# STALO_3.net
KiCad netlist of a schematic drawn in Altium Designer
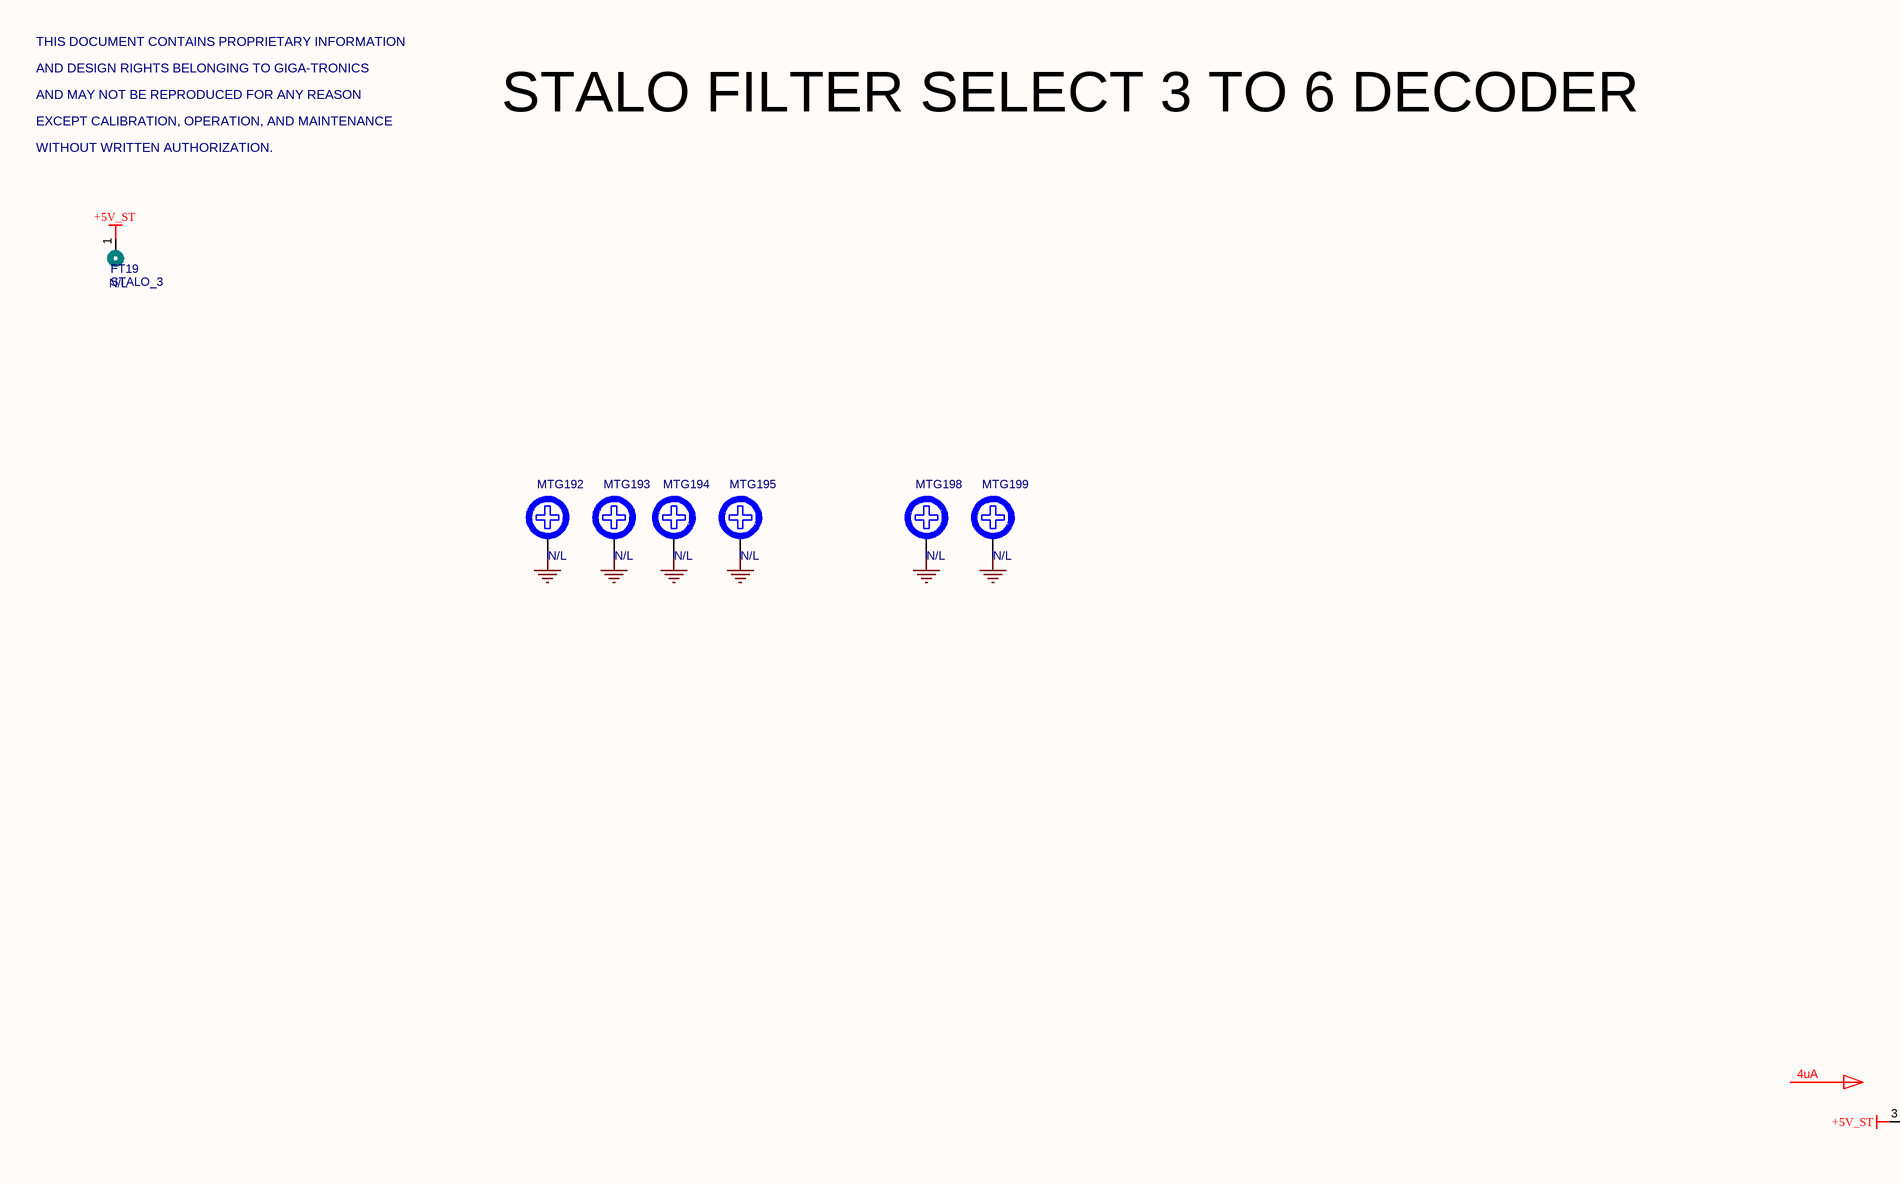
[diagram p0: STALO_3.SchDoc, top left]
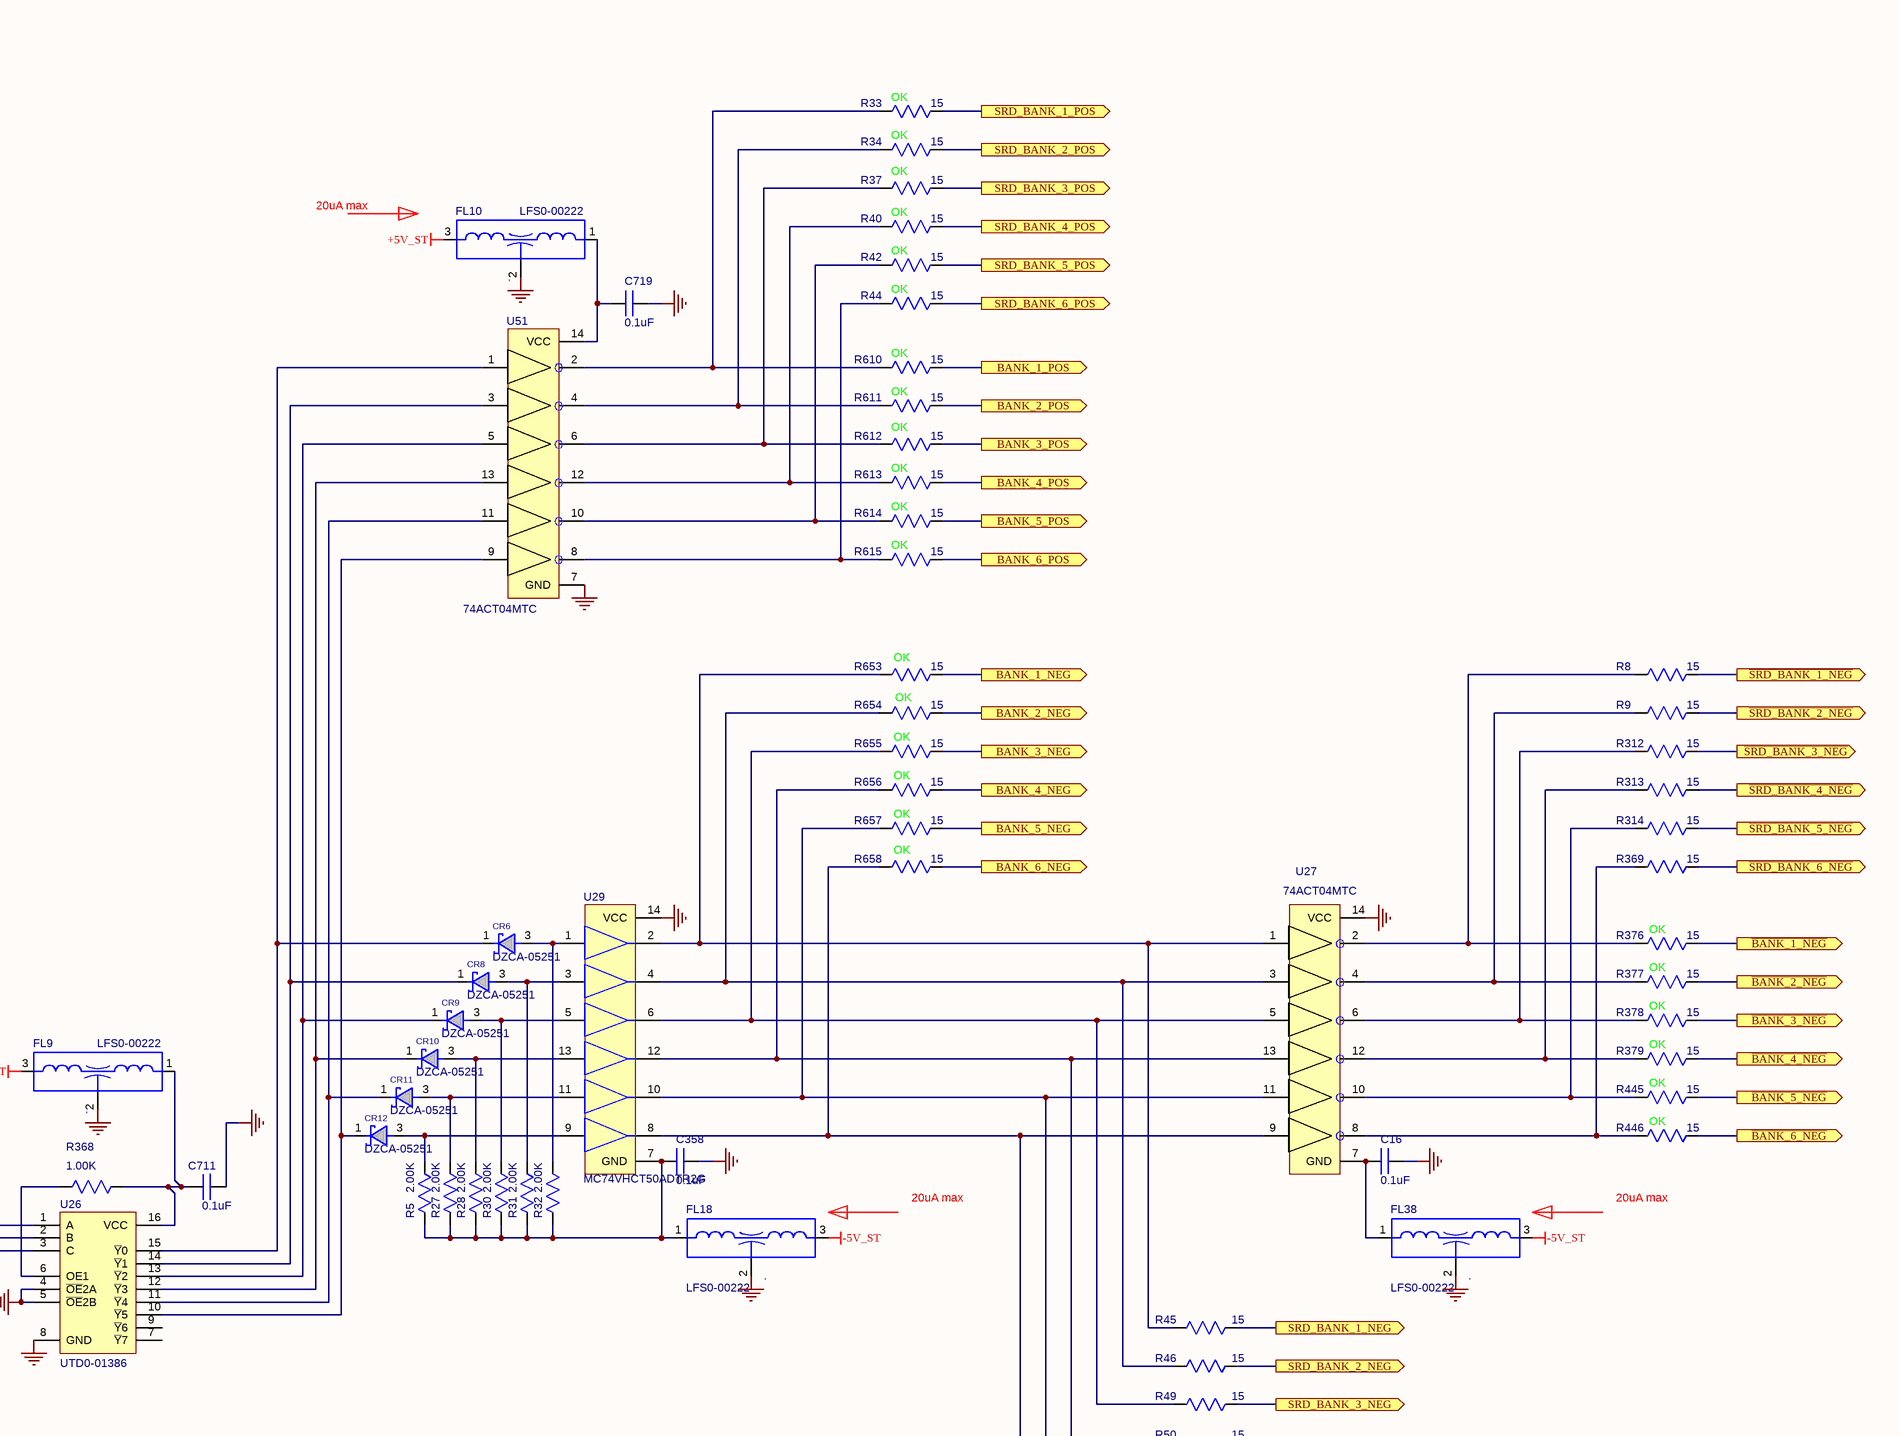
[diagram p1: STALO_3.SchDoc, top right]
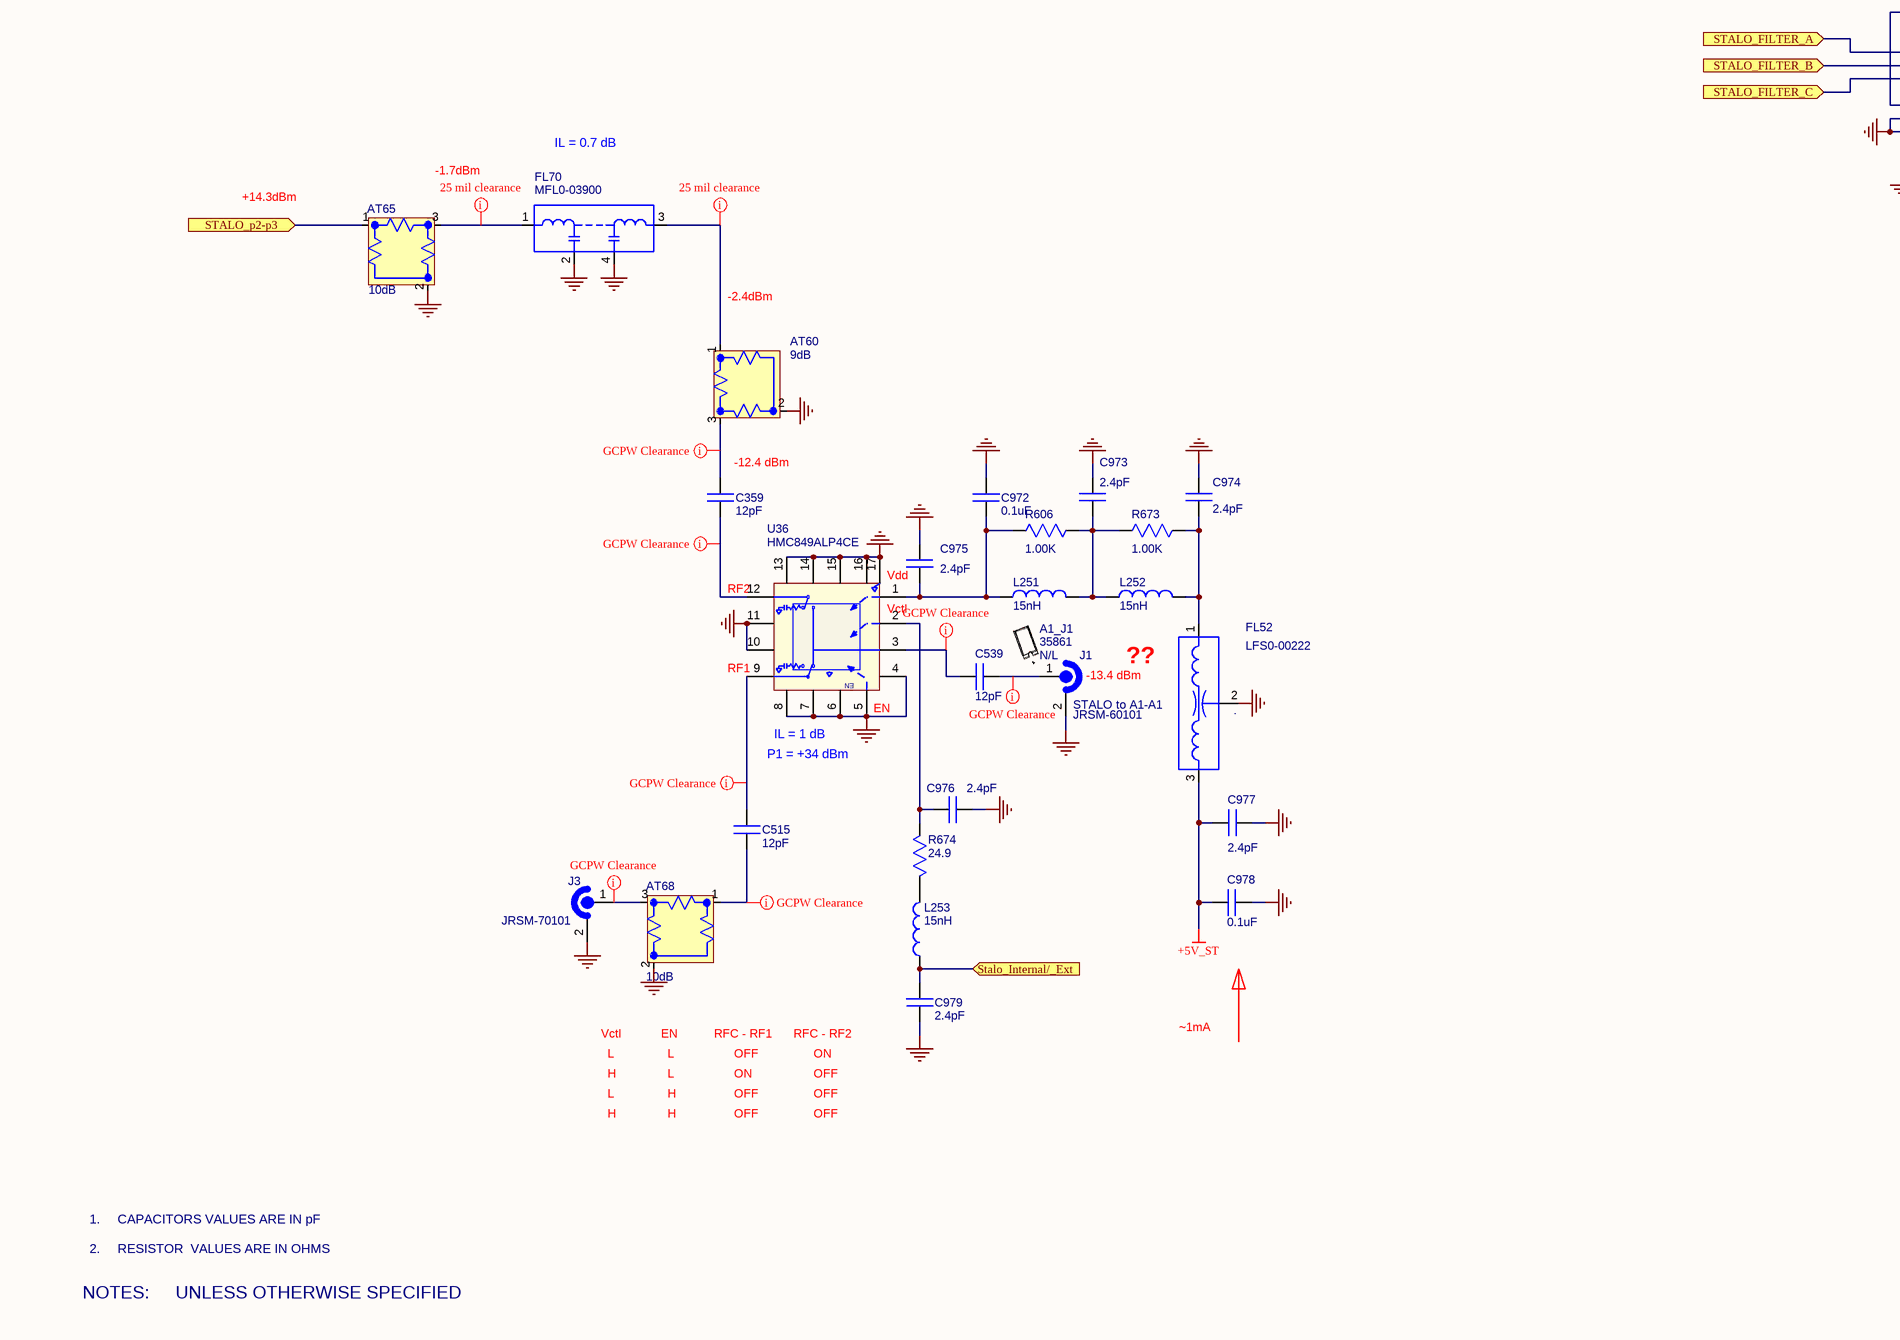
[diagram p2: STALO_3.SchDoc, bottom left]
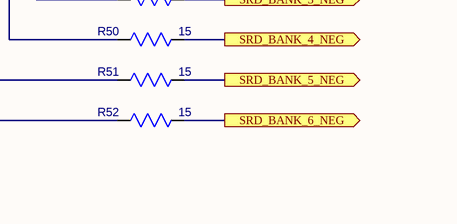
[diagram p3: STALO_3.SchDoc, bottom right]

(export (version "E")
  (design (tool "Eeschema 10.0.6"))
  (components
    (comp (ref "A1_J1")
      (value "35861")
      (footprint "35861")
      (description "SHIELD,HYDRA,A1-J1")
      (fields (field (name "NOLOAD") "N/L") (field (name "G_PN") "35861"))
      (libsource (lib "Hydra_Ref_sch") (part "35861"))
    )
    (comp (ref "AT60")
      (value "9dB")
      (footprint "ATTN-IMS-0805")
      (description "PAD;CHIP;9dB;+/-.3dB;.08 x .05;50 OHM;FACE DOWN")
      (libsource (lib "Giga-tronics") (part "MPFC-A1009"))
    )
    (comp (ref "AT65")
      (value "10dB")
      (footprint "ATTN-IMS-0805")
      (description "PAD;CHIP;10dB;+/-.3dB;.08 x .05;50 OHM;FACE DOWN")
      (libsource (lib "") (part "MPFC-A1010_1"))
    )
    (comp (ref "AT68")
      (value "10dB")
      (footprint "ATTN-IMS-0805")
      (description "PAD;CHIP;10dB;+/-.3dB;.08 x .05;50 OHM;FACE DOWN")
      (libsource (lib "Giga-tronics") (part "MPFC-A1010"))
    )
    (comp (ref "C16")
      (value "0.1uF")
      (footprint "CAP-0402-N")
      (description ".1 UF,10%;X7R;16V,CHIP;0402")
      (libsource (lib "Giga-tronics") (part "CK40-04100"))
    )
    (comp (ref "C358")
      (value "0.1uF")
      (footprint "CAP-0402-N")
      (description ".1 UF,10%;X7R;16V,CHIP;0402")
      (libsource (lib "Giga-tronics") (part "CK40-04100"))
    )
    (comp (ref "C359")
      (value "12pF")
      (footprint "CAP-0402-N")
      (description "12 PF;5%;COG;>50V;CHIP;0402")
      (libsource (lib "Giga-tronics") (part "CK40-00120"))
    )
    (comp (ref "C515")
      (value "12pF")
      (footprint "CAP-0402-N")
      (description "12 PF;5%;COG;>50V;CHIP;0402")
      (libsource (lib "Giga-tronics") (part "CK40-00120"))
    )
    (comp (ref "C539")
      (value "12pF")
      (footprint "CAP-0402-N")
      (description "12 PF;5%;COG;>50V;CHIP;0402")
      (libsource (lib "Giga-tronics") (part "CK40-00120"))
    )
    (comp (ref "C711")
      (value "0.1uF")
      (footprint "CAP-0402-N")
      (description ".1 UF,10%;X7R;16V,CHIP;0402")
      (libsource (lib "Giga-tronics") (part "CK40-04100"))
    )
    (comp (ref "C719")
      (value "0.1uF")
      (footprint "CAP-0402-N")
      (description ".1 UF,10%;X7R;16V,CHIP;0402")
      (libsource (lib "Giga-tronics") (part "CK40-04100"))
    )
    (comp (ref "C972")
      (value "0.1uF")
      (footprint "CAP-0402-N")
      (description ".1 UF,10%;X7R;16V,CHIP;0402")
      (libsource (lib "Giga-tronics") (part "CK40-04100"))
    )
    (comp (ref "C973")
      (value "2.4pF")
      (footprint "CAP-0402-RF")
      (description "2.4 PF;200V;.05PF;HIGH Q;SMT;CERAMIC;0402")
      (libsource (lib "Giga-tronics") (part "CK41-00024"))
    )
    (comp (ref "C974")
      (value "2.4pF")
      (footprint "CAP-0402-RF")
      (description "2.4 PF;200V;.05PF;HIGH Q;SMT;CERAMIC;0402")
      (libsource (lib "Giga-tronics") (part "CK41-00024"))
    )
    (comp (ref "C975")
      (value "2.4pF")
      (footprint "CAP-0402-RF")
      (description "2.4 PF;200V;.05PF;HIGH Q;SMT;CERAMIC;0402")
      (libsource (lib "Giga-tronics") (part "CK41-00024"))
    )
    (comp (ref "C976")
      (value "2.4pF")
      (footprint "CAP-0402-RF")
      (description "2.4 PF;200V;.05PF;HIGH Q;SMT;CERAMIC;0402")
      (libsource (lib "Giga-tronics") (part "CK41-00024"))
    )
    (comp (ref "C977")
      (value "2.4pF")
      (footprint "CAP-0402-RF")
      (description "2.4 PF;200V;.05PF;HIGH Q;SMT;CERAMIC;0402")
      (libsource (lib "Giga-tronics") (part "CK41-00024"))
    )
    (comp (ref "C978")
      (value "0.1uF")
      (footprint "CAP-0402-N")
      (description ".1 UF,10%;X7R;16V,CHIP;0402")
      (libsource (lib "Giga-tronics") (part "CK40-04100"))
    )
    (comp (ref "C979")
      (value "2.4pF")
      (footprint "CAP-0402-RF")
      (description "2.4 PF;200V;.05PF;HIGH Q;SMT;CERAMIC;0402")
      (libsource (lib "Giga-tronics") (part "CK41-00024"))
    )
    (comp (ref "CR6")
      (value "5.1V;5%;.15W;Z=20;0603")
      (footprint "DO-0603-SOD-523F")
      (fields (field (name "G_PN") "DZCA-05251"))
      (libsource (lib "Giga-tronics") (part "DZCA-05251"))
    )
    (comp (ref "CR8")
      (value "5.1V;5%;.15W;Z=20;0603")
      (footprint "DO-0603-SOD-523F")
      (fields (field (name "G_PN") "DZCA-05251"))
      (libsource (lib "Giga-tronics") (part "DZCA-05251"))
    )
    (comp (ref "CR9")
      (value "5.1V;5%;.15W;Z=20;0603")
      (footprint "DO-0603-SOD-523F")
      (fields (field (name "G_PN") "DZCA-05251"))
      (libsource (lib "Giga-tronics") (part "DZCA-05251"))
    )
    (comp (ref "CR10")
      (value "5.1V;5%;.15W;Z=20;0603")
      (footprint "DO-0603-SOD-523F")
      (fields (field (name "G_PN") "DZCA-05251"))
      (libsource (lib "Giga-tronics") (part "DZCA-05251"))
    )
    (comp (ref "CR11")
      (value "5.1V;5%;.15W;Z=20;0603")
      (footprint "DO-0603-SOD-523F")
      (fields (field (name "G_PN") "DZCA-05251"))
      (libsource (lib "Giga-tronics") (part "DZCA-05251"))
    )
    (comp (ref "CR12")
      (value "5.1V;5%;.15W;Z=20;0603")
      (footprint "DO-0603-SOD-523F")
      (fields (field (name "G_PN") "DZCA-05251"))
      (libsource (lib "Giga-tronics") (part "DZCA-05251"))
    )
    (comp (ref "FL9")
      (value "Filter EMI 2200PF,1206")
      (footprint "FIL-NFE31P-1206-4P")
      (fields (field (name "G_PN") "LFS0-00222"))
      (libsource (lib "Giga-tronics") (part "LFS0-00222"))
    )
    (comp (ref "FL10")
      (value "Filter EMI 2200PF,1206")
      (footprint "FIL-NFE31P-1206-4P")
      (fields (field (name "G_PN") "LFS0-00222"))
      (libsource (lib "Giga-tronics") (part "LFS0-00222"))
    )
    (comp (ref "FL18")
      (value "Filter EMI 2200PF,1206")
      (footprint "FIL-NFE31P-1206-4P")
      (fields (field (name "G_PN") "LFS0-00222"))
      (libsource (lib "") (part "LFS0-00222_1"))
    )
    (comp (ref "FL38")
      (value "Filter EMI 2200PF,1206")
      (footprint "FIL-NFE31P-1206-4P")
      (fields (field (name "G_PN") "LFS0-00222"))
      (libsource (lib "") (part "LFS0-00222_1"))
    )
    (comp (ref "FL52")
      (value "Filter EMI 2200PF,1206")
      (footprint "FIL-NFE31P-1206-4P")
      (fields (field (name "G_PN") "LFS0-00222"))
      (libsource (lib "Giga-tronics") (part "LFS0-00222"))
    )
    (comp (ref "FL70")
      (value "FILTER;LOW PASS;3900MHz;7SEC;FV1206")
      (footprint "FV1206")
      (fields (field (name "G_PN") "MFL0-03900"))
      (libsource (lib "Giga-tronics") (part "MFL0-03900"))
    )
    (comp (ref "FT19")
      (value "STALO_3")
      (footprint "FromToNode_ML2")
      (fields (field (name "NOLOAD") "N/L"))
      (libsource (lib "Giga-tronics") (part "FromToNode"))
    )
    (comp (ref "J1")
      (value "STALO to A1-A1")
      (footprint "JRSM-60101")
      (description "SMPM SM MALE,STRAIGHT SMT, R/A COPLANAR, 4 PIN THRU-HOLE")
      (fields (field (name "G_PN") "JRSM-60101"))
      (libsource (lib "Giga-tronics") (part "JRSM-60101"))
    )
    (comp (ref "J3")
      (value ".")
      (footprint "JRSM-70101")
      (description "SMPM FD MALE,STRAIGHT SMT, R/A COPLANAR, 4 PIN THRU-HOLE")
      (fields (field (name "G_PN") "JRSM-70101"))
      (libsource (lib "Giga-tronics") (part "JRSM-70101"))
    )
    (comp (ref "L251")
      (value "15nH")
      (footprint "IND-0402HP")
      (description "INDUCTOR;15NH;2%;3.9GHZ SRF;85Q @1.7GHZ;.078 DCR;1.1A;0402")
      (libsource (lib "Giga-tronics") (part "LSA6-03150"))
    )
    (comp (ref "L252")
      (value "15nH")
      (footprint "IND-0402HP")
      (description "INDUCTOR;15NH;2%;3.9GHZ SRF;85Q @1.7GHZ;.078 DCR;1.1A;0402")
      (libsource (lib "Giga-tronics") (part "LSA6-03150"))
    )
    (comp (ref "L253")
      (value "15nH")
      (footprint "IND-0402HP")
      (description "INDUCTOR;15NH;2%;3.9GHZ SRF;85Q @1.7GHZ;.078 DCR;1.1A;0402")
      (libsource (lib "") (part "LSA6-03150_1"))
    )
    (comp (ref "MTG192")
      (value "~")
      (footprint "MHP200X92")
      (description "MHP200X92")
      (fields (field (name "NOLOAD") "N/L"))
      (libsource (lib "Giga-tronics") (part "MHP200X92"))
    )
    (comp (ref "MTG193")
      (value "~")
      (footprint "MHP200X92")
      (description "MHP200X92")
      (fields (field (name "NOLOAD") "N/L"))
      (libsource (lib "Giga-tronics") (part "MHP200X92"))
    )
    (comp (ref "MTG194")
      (value "~")
      (footprint "MHP200X92")
      (description "MHP200X92")
      (fields (field (name "NOLOAD") "N/L"))
      (libsource (lib "Giga-tronics") (part "MHP200X92"))
    )
    (comp (ref "MTG195")
      (value "~")
      (footprint "MHP200X92")
      (description "MHP200X92")
      (fields (field (name "NOLOAD") "N/L"))
      (libsource (lib "Giga-tronics") (part "MHP200X92"))
    )
    (comp (ref "MTG198")
      (value "~")
      (footprint "MHP200X92")
      (description "MHP200X92")
      (fields (field (name "NOLOAD") "N/L"))
      (libsource (lib "Giga-tronics") (part "MHP200X92"))
    )
    (comp (ref "MTG199")
      (value "~")
      (footprint "MHP200X92")
      (description "MHP200X92")
      (fields (field (name "NOLOAD") "N/L"))
      (libsource (lib "Giga-tronics") (part "MHP200X92"))
    )
    (comp (ref "R5")
      (value "2.00K")
      (footprint "RES-0402-N")
      (description "2.00K OHMS;.06W;1%;200PPM;FILM;CHIP;0402")
      (libsource (lib "Giga-tronics") (part "RK35-12000"))
    )
    (comp (ref "R8")
      (value "15")
      (footprint "RES-0402-N")
      (description "15 OHMS;.06W;1%;200PPM;FILM;CHIP;0402")
      (libsource (lib "Giga-tronics") (part "RK35-00150"))
    )
    (comp (ref "R9")
      (value "15")
      (footprint "RES-0402-N")
      (description "15 OHMS;.06W;1%;200PPM;FILM;CHIP;0402")
      (libsource (lib "Giga-tronics") (part "RK35-00150"))
    )
    (comp (ref "R27")
      (value "2.00K")
      (footprint "RES-0402-N")
      (description "2.00K OHMS;.06W;1%;200PPM;FILM;CHIP;0402")
      (libsource (lib "Giga-tronics") (part "RK35-12000"))
    )
    (comp (ref "R28")
      (value "2.00K")
      (footprint "RES-0402-N")
      (description "2.00K OHMS;.06W;1%;200PPM;FILM;CHIP;0402")
      (libsource (lib "Giga-tronics") (part "RK35-12000"))
    )
    (comp (ref "R30")
      (value "2.00K")
      (footprint "RES-0402-N")
      (description "2.00K OHMS;.06W;1%;200PPM;FILM;CHIP;0402")
      (libsource (lib "Giga-tronics") (part "RK35-12000"))
    )
    (comp (ref "R31")
      (value "2.00K")
      (footprint "RES-0402-N")
      (description "2.00K OHMS;.06W;1%;200PPM;FILM;CHIP;0402")
      (libsource (lib "Giga-tronics") (part "RK35-12000"))
    )
    (comp (ref "R32")
      (value "2.00K")
      (footprint "RES-0402-N")
      (description "2.00K OHMS;.06W;1%;200PPM;FILM;CHIP;0402")
      (libsource (lib "Giga-tronics") (part "RK35-12000"))
    )
    (comp (ref "R33")
      (value "15")
      (footprint "RES-0402-N")
      (description "15 OHMS;.06W;1%;200PPM;FILM;CHIP;0402")
      (libsource (lib "Giga-tronics") (part "RK35-00150"))
    )
    (comp (ref "R34")
      (value "15")
      (footprint "RES-0402-N")
      (description "15 OHMS;.06W;1%;200PPM;FILM;CHIP;0402")
      (libsource (lib "Giga-tronics") (part "RK35-00150"))
    )
    (comp (ref "R37")
      (value "15")
      (footprint "RES-0402-N")
      (description "15 OHMS;.06W;1%;200PPM;FILM;CHIP;0402")
      (libsource (lib "Giga-tronics") (part "RK35-00150"))
    )
    (comp (ref "R40")
      (value "15")
      (footprint "RES-0402-N")
      (description "15 OHMS;.06W;1%;200PPM;FILM;CHIP;0402")
      (libsource (lib "Giga-tronics") (part "RK35-00150"))
    )
    (comp (ref "R42")
      (value "15")
      (footprint "RES-0402-N")
      (description "15 OHMS;.06W;1%;200PPM;FILM;CHIP;0402")
      (libsource (lib "Giga-tronics") (part "RK35-00150"))
    )
    (comp (ref "R44")
      (value "15")
      (footprint "RES-0402-N")
      (description "15 OHMS;.06W;1%;200PPM;FILM;CHIP;0402")
      (libsource (lib "Giga-tronics") (part "RK35-00150"))
    )
    (comp (ref "R45")
      (value "15")
      (footprint "RES-0402-N")
      (description "15 OHMS;.06W;1%;200PPM;FILM;CHIP;0402")
      (libsource (lib "Giga-tronics") (part "RK35-00150"))
    )
    (comp (ref "R46")
      (value "15")
      (footprint "RES-0402-N")
      (description "15 OHMS;.06W;1%;200PPM;FILM;CHIP;0402")
      (libsource (lib "Giga-tronics") (part "RK35-00150"))
    )
    (comp (ref "R49")
      (value "15")
      (footprint "RES-0402-N")
      (description "15 OHMS;.06W;1%;200PPM;FILM;CHIP;0402")
      (libsource (lib "Giga-tronics") (part "RK35-00150"))
    )
    (comp (ref "R50")
      (value "15")
      (footprint "RES-0402-N")
      (description "15 OHMS;.06W;1%;200PPM;FILM;CHIP;0402")
      (libsource (lib "Giga-tronics") (part "RK35-00150"))
    )
    (comp (ref "R51")
      (value "15")
      (footprint "RES-0402-N")
      (description "15 OHMS;.06W;1%;200PPM;FILM;CHIP;0402")
      (libsource (lib "Giga-tronics") (part "RK35-00150"))
    )
    (comp (ref "R52")
      (value "15")
      (footprint "RES-0402-N")
      (description "15 OHMS;.06W;1%;200PPM;FILM;CHIP;0402")
      (libsource (lib "Giga-tronics") (part "RK35-00150"))
    )
    (comp (ref "R312")
      (value "15")
      (footprint "RES-0402-N")
      (description "15 OHMS;.06W;1%;200PPM;FILM;CHIP;0402")
      (libsource (lib "Giga-tronics") (part "RK35-00150"))
    )
    (comp (ref "R313")
      (value "15")
      (footprint "RES-0402-N")
      (description "15 OHMS;.06W;1%;200PPM;FILM;CHIP;0402")
      (libsource (lib "Giga-tronics") (part "RK35-00150"))
    )
    (comp (ref "R314")
      (value "15")
      (footprint "RES-0402-N")
      (description "15 OHMS;.06W;1%;200PPM;FILM;CHIP;0402")
      (libsource (lib "Giga-tronics") (part "RK35-00150"))
    )
    (comp (ref "R368")
      (value "1.00K")
      (footprint "RES-0402-N")
      (description "1.0K OHMS;.06W;1%;200PPM;FILM;CHIP;0402")
      (libsource (lib "Giga-tronics") (part "RK35-11000"))
    )
    (comp (ref "R369")
      (value "15")
      (footprint "RES-0402-N")
      (description "15 OHMS;.06W;1%;200PPM;FILM;CHIP;0402")
      (libsource (lib "Giga-tronics") (part "RK35-00150"))
    )
    (comp (ref "R376")
      (value "15")
      (footprint "RES-0402-N")
      (description "15 OHMS;.06W;1%;200PPM;FILM;CHIP;0402")
      (libsource (lib "Giga-tronics") (part "RK35-00150"))
    )
    (comp (ref "R377")
      (value "15")
      (footprint "RES-0402-N")
      (description "15 OHMS;.06W;1%;200PPM;FILM;CHIP;0402")
      (libsource (lib "Giga-tronics") (part "RK35-00150"))
    )
    (comp (ref "R378")
      (value "15")
      (footprint "RES-0402-N")
      (description "15 OHMS;.06W;1%;200PPM;FILM;CHIP;0402")
      (libsource (lib "Giga-tronics") (part "RK35-00150"))
    )
    (comp (ref "R379")
      (value "15")
      (footprint "RES-0402-N")
      (description "15 OHMS;.06W;1%;200PPM;FILM;CHIP;0402")
      (libsource (lib "Giga-tronics") (part "RK35-00150"))
    )
    (comp (ref "R445")
      (value "15")
      (footprint "RES-0402-N")
      (description "15 OHMS;.06W;1%;200PPM;FILM;CHIP;0402")
      (libsource (lib "Giga-tronics") (part "RK35-00150"))
    )
    (comp (ref "R446")
      (value "15")
      (footprint "RES-0402-N")
      (description "15 OHMS;.06W;1%;200PPM;FILM;CHIP;0402")
      (libsource (lib "Giga-tronics") (part "RK35-00150"))
    )
    (comp (ref "R606")
      (value "1.00K")
      (footprint "RES-0402-N")
      (description "1.0K OHMS;.06W;1%;200PPM;FILM;CHIP;0402")
      (libsource (lib "Giga-tronics") (part "RK35-11000"))
    )
    (comp (ref "R610")
      (value "15")
      (footprint "RES-0402-N")
      (description "15 OHMS;.06W;1%;200PPM;FILM;CHIP;0402")
      (libsource (lib "Giga-tronics") (part "RK35-00150"))
    )
    (comp (ref "R611")
      (value "15")
      (footprint "RES-0402-N")
      (description "15 OHMS;.06W;1%;200PPM;FILM;CHIP;0402")
      (libsource (lib "Giga-tronics") (part "RK35-00150"))
    )
    (comp (ref "R612")
      (value "15")
      (footprint "RES-0402-N")
      (description "15 OHMS;.06W;1%;200PPM;FILM;CHIP;0402")
      (libsource (lib "Giga-tronics") (part "RK35-00150"))
    )
    (comp (ref "R613")
      (value "15")
      (footprint "RES-0402-N")
      (description "15 OHMS;.06W;1%;200PPM;FILM;CHIP;0402")
      (libsource (lib "Giga-tronics") (part "RK35-00150"))
    )
    (comp (ref "R614")
      (value "15")
      (footprint "RES-0402-N")
      (description "15 OHMS;.06W;1%;200PPM;FILM;CHIP;0402")
      (libsource (lib "Giga-tronics") (part "RK35-00150"))
    )
    (comp (ref "R615")
      (value "15")
      (footprint "RES-0402-N")
      (description "15 OHMS;.06W;1%;200PPM;FILM;CHIP;0402")
      (libsource (lib "Giga-tronics") (part "RK35-00150"))
    )
    (comp (ref "R653")
      (value "15")
      (footprint "RES-0402-N")
      (description "15 OHMS;.06W;1%;200PPM;FILM;CHIP;0402")
      (libsource (lib "Giga-tronics") (part "RK35-00150"))
    )
    (comp (ref "R654")
      (value "15")
      (footprint "RES-0402-N")
      (description "15 OHMS;.06W;1%;200PPM;FILM;CHIP;0402")
      (libsource (lib "Giga-tronics") (part "RK35-00150"))
    )
    (comp (ref "R655")
      (value "15")
      (footprint "RES-0402-N")
      (description "15 OHMS;.06W;1%;200PPM;FILM;CHIP;0402")
      (libsource (lib "Giga-tronics") (part "RK35-00150"))
    )
    (comp (ref "R656")
      (value "15")
      (footprint "RES-0402-N")
      (description "15 OHMS;.06W;1%;200PPM;FILM;CHIP;0402")
      (libsource (lib "Giga-tronics") (part "RK35-00150"))
    )
    (comp (ref "R657")
      (value "15")
      (footprint "RES-0402-N")
      (description "15 OHMS;.06W;1%;200PPM;FILM;CHIP;0402")
      (libsource (lib "Giga-tronics") (part "RK35-00150"))
    )
    (comp (ref "R658")
      (value "15")
      (footprint "RES-0402-N")
      (description "15 OHMS;.06W;1%;200PPM;FILM;CHIP;0402")
      (libsource (lib "Giga-tronics") (part "RK35-00150"))
    )
    (comp (ref "R673")
      (value "1.00K")
      (footprint "RES-0402-N")
      (description "1.0K OHMS;.06W;1%;200PPM;FILM;CHIP;0402")
      (libsource (lib "Giga-tronics") (part "RK35-11000"))
    )
    (comp (ref "R674")
      (value "24.9")
      (footprint "RES-0402-N")
      (description "24.9 OHMS;.06W;1%;200PPM;FILM;CHIP;0402")
      (libsource (lib "Giga-tronics") (part "RK35-00249"))
    )
    (comp (ref "U26")
      (value "UTD0-01386")
      (footprint "SOIC16_MS-012")
      (description "3 TO 8 DECODER/DEMULTIPLEXER;74ACT138 LOGIC;SO-16")
      (fields (field (name "G_PN") "UTD0-01386"))
      (libsource (lib "Giga-tronics") (part "UTD0-01386"))
    )
    (comp (ref "U27")
      (value "74ACT04MTC HEX INVERTER;SMT;TSSOP-14")
      (footprint "TSOP65P640X120-14L")
      (fields (field (name "M_PN") "74ACT04MTC"))
      (libsource (lib "Giga-tronics") (part "UTD4-00046"))
    )
    (comp (ref "U29")
      (value "MC74VHCT50A;HEX BUFFERS;3.5NS;TTL INPUTS;TSSOP-14")
      (footprint "TSOP65P640X120-14L")
      (fields (field (name "M_PN") "MC74VHCT50ADTR2G"))
      (libsource (lib "Giga-tronics") (part "UTD0-00050"))
    )
    (comp (ref "U36")
      (value "SWITCH;SPDT;DC-6GHz;50DB ISO;33DBM;3-5V CTRL;QFN-16")
      (footprint "QFN-16_HITTITE_LP4CE")
      (fields (field (name "M_PN") "HMC849ALP4CE"))
      (libsource (lib "Giga-tronics") (part "MRSS-12206"))
    )
    (comp (ref "U51")
      (value "74ACT04MTC HEX INVERTER;SMT;TSSOP-14")
      (footprint "TSOP65P640X120-14L")
      (fields (field (name "M_PN") "74ACT04MTC"))
      (libsource (lib "Giga-tronics") (part "UTD4-00046"))
    )
  )
  (nets
    (net (code "1") (name "+5V_ST") (class "Default")
      (node (ref "C977") (pin "2") (pintype "passive"))
      (node (ref "C978") (pin "1") (pintype "passive"))
      (node (ref "FL10") (pin "3") (pinfunction "OUT_3") (pintype "passive"))
      (node (ref "FL52") (pin "3") (pinfunction "OUT_3") (pintype "passive"))
      (node (ref "FL9") (pin "3") (pinfunction "OUT_3") (pintype "passive"))
      (node (ref "FT19") (pin "1") (pinfunction "1_1") (pintype "passive"))
    )
    (net (code "2") (name "-5V_ST") (class "Default")
      (node (ref "FL18") (pin "3") (pinfunction "OUT_3") (pintype "passive"))
      (node (ref "FL38") (pin "3") (pinfunction "OUT_3") (pintype "passive"))
    )
    (net (code "3") (name "/BANK_1_NEG") (class "Default") (node (ref "R653") (pin "2") (pintype "passive")))
    (net (code "4") (name "/BANK_1_POS") (class "Default") (node (ref "R610") (pin "2") (pintype "passive")))
    (net (code "5") (name "/BANK_2_NEG") (class "Default") (node (ref "R654") (pin "2") (pintype "passive")))
    (net (code "6") (name "/BANK_2_POS") (class "Default") (node (ref "R611") (pin "2") (pintype "passive")))
    (net (code "7") (name "/BANK_3_NEG") (class "Default") (node (ref "R655") (pin "2") (pintype "passive")))
    (net (code "8") (name "/BANK_3_POS") (class "Default") (node (ref "R612") (pin "2") (pintype "passive")))
    (net (code "9") (name "/BANK_4_NEG") (class "Default") (node (ref "R656") (pin "2") (pintype "passive")))
    (net (code "10") (name "/BANK_4_POS") (class "Default") (node (ref "R613") (pin "2") (pintype "passive")))
    (net (code "11") (name "/BANK_5_NEG") (class "Default") (node (ref "R657") (pin "2") (pintype "passive")))
    (net (code "12") (name "/BANK_5_POS") (class "Default") (node (ref "R614") (pin "2") (pintype "passive")))
    (net (code "13") (name "/BANK_6_NEG") (class "Default") (node (ref "R658") (pin "2") (pintype "passive")))
    (net (code "14") (name "/BANK_6_POS") (class "Default") (node (ref "R615") (pin "2") (pintype "passive")))
    (net (code "15") (name "/SRD_BANK_1_NEG") (class "Default")
      (node (ref "R45") (pin "2") (pintype "passive"))
    )
    (net (code "16") (name "/SRD_BANK_1_POS") (class "Default")
      (node (ref "R33") (pin "2") (pintype "passive"))
    )
    (net (code "17") (name "/SRD_BANK_2_NEG") (class "Default")
      (node (ref "R46") (pin "2") (pintype "passive"))
    )
    (net (code "18") (name "/SRD_BANK_2_POS") (class "Default")
      (node (ref "R34") (pin "2") (pintype "passive"))
    )
    (net (code "19") (name "/SRD_BANK_3_NEG") (class "Default")
      (node (ref "R49") (pin "2") (pintype "passive"))
    )
    (net (code "20") (name "/SRD_BANK_3_POS") (class "Default")
      (node (ref "R37") (pin "2") (pintype "passive"))
    )
    (net (code "21") (name "/SRD_BANK_4_NEG") (class "Default")
      (node (ref "R50") (pin "2") (pintype "passive"))
    )
    (net (code "22") (name "/SRD_BANK_4_POS") (class "Default")
      (node (ref "R40") (pin "2") (pintype "passive"))
    )
    (net (code "23") (name "/SRD_BANK_5_NEG") (class "Default")
      (node (ref "R51") (pin "2") (pintype "passive"))
    )
    (net (code "24") (name "/SRD_BANK_5_POS") (class "Default")
      (node (ref "R42") (pin "2") (pintype "passive"))
    )
    (net (code "25") (name "/SRD_BANK_6_NEG") (class "Default")
      (node (ref "R52") (pin "2") (pintype "passive"))
    )
    (net (code "26") (name "/SRD_BANK_6_POS") (class "Default")
      (node (ref "R44") (pin "2") (pintype "passive"))
    )
    (net (code "27") (name "/STALO_FILTER_A") (class "Default")
      (node (ref "U26") (pin "1") (pinfunction "A_1") (pintype "passive"))
    )
    (net (code "28") (name "/STALO_FILTER_B") (class "Default")
      (node (ref "U26") (pin "2") (pinfunction "B_2") (pintype "passive"))
    )
    (net (code "29") (name "/STALO_FILTER_C") (class "Default")
      (node (ref "U26") (pin "3") (pinfunction "C_3") (pintype "passive"))
    )
    (net (code "30") (name "/STALO_p2-p3") (class "Default")
      (node (ref "AT65") (pin "1") (pinfunction "IN/OUT_1") (pintype "passive"))
    )
    (net (code "31") (name "/Stalo_Internal{slash}_Ext") (class "Default")
      (node (ref "C979") (pin "2") (pintype "passive"))
      (node (ref "L253") (pin "2") (pinfunction "2_2") (pintype "passive"))
    )
    (net (code "32") (name "/~{BANK_1_NEG}") (class "Default")
      (node (ref "R376") (pin "2") (pintype "passive"))
    )
    (net (code "33") (name "/~{BANK_2_NEG}") (class "Default")
      (node (ref "R377") (pin "2") (pintype "passive"))
    )
    (net (code "34") (name "/~{BANK_3_NEG}") (class "Default")
      (node (ref "R378") (pin "2") (pintype "passive"))
    )
    (net (code "35") (name "/~{BANK_4_NEG}") (class "Default")
      (node (ref "R379") (pin "2") (pintype "passive"))
    )
    (net (code "36") (name "/~{BANK_5_NEG}") (class "Default")
      (node (ref "R445") (pin "2") (pintype "passive"))
    )
    (net (code "37") (name "/~{BANK_6_NEG}") (class "Default")
      (node (ref "R446") (pin "2") (pintype "passive"))
    )
    (net (code "38") (name "/~{SRD_BANK_1_NEG}") (class "Default")
      (node (ref "R8") (pin "2") (pintype "passive"))
    )
    (net (code "39") (name "/~{SRD_BANK_2_NEG}") (class "Default")
      (node (ref "R9") (pin "2") (pintype "passive"))
    )
    (net (code "40") (name "/~{SRD_BANK_3_NEG}") (class "Default")
      (node (ref "R312") (pin "2") (pintype "passive"))
    )
    (net (code "41") (name "/~{SRD_BANK_4_NEG}") (class "Default")
      (node (ref "R313") (pin "2") (pintype "passive"))
    )
    (net (code "42") (name "/~{SRD_BANK_5_NEG}") (class "Default")
      (node (ref "R314") (pin "2") (pintype "passive"))
    )
    (net (code "43") (name "/~{SRD_BANK_6_NEG}") (class "Default")
      (node (ref "R369") (pin "2") (pintype "passive"))
    )
    (net (code "44") (name "GND") (class "Default")
      (node (ref "AT60") (pin "2") (pinfunction "GND_2") (pintype "power_in"))
      (node (ref "AT65") (pin "2") (pinfunction "GND_2") (pintype "power_in"))
      (node (ref "AT68") (pin "2") (pinfunction "GND_2") (pintype "power_in"))
      (node (ref "C16") (pin "2") (pintype "passive"))
      (node (ref "C358") (pin "2") (pintype "passive"))
      (node (ref "C711") (pin "2") (pintype "passive"))
      (node (ref "C719") (pin "2") (pintype "passive"))
      (node (ref "C972") (pin "2") (pintype "passive"))
      (node (ref "C973") (pin "1") (pintype "passive"))
      (node (ref "C974") (pin "1") (pintype "passive"))
      (node (ref "C975") (pin "1") (pintype "passive"))
      (node (ref "C976") (pin "2") (pintype "passive"))
      (node (ref "C977") (pin "1") (pintype "passive"))
      (node (ref "C978") (pin "2") (pintype "passive"))
      (node (ref "C979") (pin "1") (pintype "passive"))
      (node (ref "FL10") (pin "2") (pinfunction "GND_2") (pintype "passive"))
      (node (ref "FL18") (pin "2") (pinfunction "GND_2") (pintype "passive"))
      (node (ref "FL38") (pin "2") (pinfunction "GND_2") (pintype "passive"))
      (node (ref "FL52") (pin "2") (pinfunction "GND_2") (pintype "passive"))
      (node (ref "FL70") (pin "2") (pinfunction "OUT_2") (pintype "passive"))
      (node (ref "FL70") (pin "4") (pinfunction "GND_4") (pintype "passive"))
      (node (ref "FL9") (pin "2") (pinfunction "GND_2") (pintype "passive"))
      (node (ref "J1") (pin "2") (pinfunction "GND_2") (pintype "passive"))
      (node (ref "J3") (pin "2") (pinfunction "GND_2") (pintype "passive"))
      (node (ref "MTG192") (pin "MH") (pintype "passive"))
      (node (ref "MTG193") (pin "MH") (pintype "passive"))
      (node (ref "MTG194") (pin "MH") (pintype "passive"))
      (node (ref "MTG195") (pin "MH") (pintype "passive"))
      (node (ref "MTG198") (pin "MH") (pintype "passive"))
      (node (ref "MTG199") (pin "MH") (pintype "passive"))
      (node (ref "U26") (pin "4") (pinfunction "~{OE}2A_4") (pintype "passive"))
      (node (ref "U26") (pin "5") (pinfunction "~{OE}2B_5") (pintype "passive"))
      (node (ref "U26") (pin "8") (pinfunction "GND_8") (pintype "passive"))
      (node (ref "U27") (pin "14") (pinfunction "VCC_14") (pintype "passive"))
      (node (ref "U29") (pin "14") (pinfunction "VCC_14") (pintype "passive"))
      (node (ref "U36") (pin "10") (pinfunction "GND_10") (pintype "passive"))
      (node (ref "U36") (pin "11") (pinfunction "GND_11") (pintype "passive"))
      (node (ref "U36") (pin "13") (pinfunction "NC_13") (pintype "passive"))
      (node (ref "U36") (pin "14") (pinfunction "NC_14") (pintype "passive"))
      (node (ref "U36") (pin "15") (pinfunction "NC_15") (pintype "passive"))
      (node (ref "U36") (pin "16") (pinfunction "NC_16") (pintype "passive"))
      (node (ref "U36") (pin "17") (pinfunction "GND_17") (pintype "passive"))
      (node (ref "U36") (pin "4") (pinfunction "NC_4") (pintype "passive"))
      (node (ref "U36") (pin "5") (pinfunction "EN_5") (pintype "passive"))
      (node (ref "U36") (pin "6") (pinfunction "NC_6") (pintype "passive"))
      (node (ref "U36") (pin "7") (pinfunction "NC_7") (pintype "passive"))
      (node (ref "U36") (pin "8") (pinfunction "NC_8") (pintype "passive"))
      (node (ref "U51") (pin "7") (pinfunction "GND_7") (pintype "passive"))
    )
    (net (code "45") (name "Net-(AT60-IN{slash}OUT-Pad1)") (class "Default")
      (node (ref "AT60") (pin "1") (pinfunction "IN/OUT_1") (pintype "passive"))
      (node (ref "FL70") (pin "3") (pinfunction "GND_3") (pintype "passive"))
    )
    (net (code "46") (name "Net-(AT60-IN{slash}OUT-Pad3)") (class "Default")
      (node (ref "AT60") (pin "3") (pinfunction "IN/OUT_3") (pintype "passive"))
      (node (ref "C359") (pin "2") (pintype "passive"))
    )
    (net (code "47") (name "Net-(AT68-IN{slash}OUT-Pad1)") (class "Default")
      (node (ref "AT68") (pin "1") (pinfunction "IN/OUT_1") (pintype "passive"))
      (node (ref "C515") (pin "1") (pintype "passive"))
    )
    (net (code "48") (name "Net-(C973-Pad2)") (class "Default")
      (node (ref "C973") (pin "2") (pintype "passive"))
      (node (ref "L251") (pin "2") (pinfunction "2_2") (pintype "passive"))
      (node (ref "L252") (pin "1") (pinfunction "1_1") (pintype "passive"))
      (node (ref "R606") (pin "2") (pintype "passive"))
      (node (ref "R673") (pin "1") (pintype "passive"))
    )
    (net (code "49") (name "Net-(CR6-A)") (class "Default")
      (node (ref "CR6") (pin "3") (pinfunction "A_3") (pintype "passive"))
      (node (ref "R32") (pin "2") (pintype "passive"))
      (node (ref "U29") (pin "1") (pintype "passive"))
    )
    (net (code "50") (name "Net-(CR6-K)") (class "Default")
      (node (ref "CR6") (pin "1") (pinfunction "K_1") (pintype "passive"))
      (node (ref "U26") (pin "15") (pinfunction "~{Y}0_15") (pintype "passive"))
      (node (ref "U51") (pin "1") (pintype "passive"))
    )
    (net (code "51") (name "Net-(CR8-A)") (class "Default")
      (node (ref "CR8") (pin "3") (pinfunction "A_3") (pintype "passive"))
      (node (ref "R31") (pin "2") (pintype "passive"))
      (node (ref "U29") (pin "3") (pintype "passive"))
    )
    (net (code "52") (name "Net-(CR8-K)") (class "Default")
      (node (ref "CR8") (pin "1") (pinfunction "K_1") (pintype "passive"))
      (node (ref "U26") (pin "14") (pinfunction "~{Y}1_14") (pintype "passive"))
      (node (ref "U51") (pin "3") (pintype "passive"))
    )
    (net (code "53") (name "Net-(CR9-A)") (class "Default")
      (node (ref "CR9") (pin "3") (pinfunction "A_3") (pintype "passive"))
      (node (ref "R30") (pin "2") (pintype "passive"))
      (node (ref "U29") (pin "5") (pintype "passive"))
    )
    (net (code "54") (name "Net-(CR9-K)") (class "Default")
      (node (ref "CR9") (pin "1") (pinfunction "K_1") (pintype "passive"))
      (node (ref "U26") (pin "13") (pinfunction "~{Y}2_13") (pintype "passive"))
      (node (ref "U51") (pin "5") (pintype "passive"))
    )
    (net (code "55") (name "Net-(CR10-A)") (class "Default")
      (node (ref "CR10") (pin "3") (pinfunction "A_3") (pintype "passive"))
      (node (ref "R28") (pin "2") (pintype "passive"))
      (node (ref "U29") (pin "13") (pintype "passive"))
    )
    (net (code "56") (name "Net-(CR10-K)") (class "Default")
      (node (ref "CR10") (pin "1") (pinfunction "K_1") (pintype "passive"))
      (node (ref "U26") (pin "12") (pinfunction "~{Y}3_12") (pintype "passive"))
      (node (ref "U51") (pin "13") (pintype "passive"))
    )
    (net (code "57") (name "Net-(CR11-A)") (class "Default")
      (node (ref "CR11") (pin "3") (pinfunction "A_3") (pintype "passive"))
      (node (ref "R27") (pin "2") (pintype "passive"))
      (node (ref "U29") (pin "11") (pintype "passive"))
    )
    (net (code "58") (name "Net-(CR11-K)") (class "Default")
      (node (ref "CR11") (pin "1") (pinfunction "K_1") (pintype "passive"))
      (node (ref "U26") (pin "11") (pinfunction "~{Y}4_11") (pintype "passive"))
      (node (ref "U51") (pin "11") (pintype "passive"))
    )
    (net (code "59") (name "Net-(CR12-A)") (class "Default")
      (node (ref "CR12") (pin "3") (pinfunction "A_3") (pintype "passive"))
      (node (ref "R5") (pin "2") (pintype "passive"))
      (node (ref "U29") (pin "9") (pintype "passive"))
    )
    (net (code "60") (name "Net-(CR12-K)") (class "Default")
      (node (ref "CR12") (pin "1") (pinfunction "K_1") (pintype "passive"))
      (node (ref "U26") (pin "10") (pinfunction "~{Y}5_10") (pintype "passive"))
      (node (ref "U51") (pin "9") (pintype "passive"))
    )
    (net (code "61") (name "Net-(FL9-IN)") (class "Default")
      (node (ref "C711") (pin "1") (pintype "passive"))
      (node (ref "FL9") (pin "1") (pinfunction "IN_1") (pintype "passive"))
      (node (ref "R368") (pin "2") (pintype "passive"))
      (node (ref "U26") (pin "16") (pinfunction "VCC_16") (pintype "passive"))
    )
    (net (code "62") (name "Net-(FL10-IN)") (class "Default")
      (node (ref "C719") (pin "1") (pintype "passive"))
      (node (ref "FL10") (pin "1") (pinfunction "IN_1") (pintype "passive"))
      (node (ref "U51") (pin "14") (pinfunction "VCC_14") (pintype "passive"))
    )
    (net (code "63") (name "Net-(FL18-IN)") (class "Default")
      (node (ref "C358") (pin "1") (pintype "passive"))
      (node (ref "FL18") (pin "1") (pinfunction "IN_1") (pintype "passive"))
      (node (ref "R27") (pin "1") (pintype "passive"))
      (node (ref "R28") (pin "1") (pintype "passive"))
      (node (ref "R30") (pin "1") (pintype "passive"))
      (node (ref "R31") (pin "1") (pintype "passive"))
      (node (ref "R32") (pin "1") (pintype "passive"))
      (node (ref "R5") (pin "1") (pintype "passive"))
      (node (ref "U29") (pin "7") (pinfunction "GND_7") (pintype "passive"))
    )
    (net (code "64") (name "Net-(FL38-IN)") (class "Default")
      (node (ref "C16") (pin "1") (pintype "passive"))
      (node (ref "FL38") (pin "1") (pinfunction "IN_1") (pintype "passive"))
      (node (ref "U27") (pin "7") (pinfunction "GND_7") (pintype "passive"))
    )
    (net (code "65") (name "Net-(FL52-IN)") (class "Default")
      (node (ref "C974") (pin "2") (pintype "passive"))
      (node (ref "FL52") (pin "1") (pinfunction "IN_1") (pintype "passive"))
      (node (ref "L252") (pin "2") (pinfunction "2_2") (pintype "passive"))
      (node (ref "R673") (pin "2") (pintype "passive"))
    )
    (net (code "66") (name "Net-(FL70-IN)") (class "Default")
      (node (ref "AT65") (pin "3") (pinfunction "IN/OUT_3") (pintype "passive"))
      (node (ref "FL70") (pin "1") (pinfunction "IN_1") (pintype "passive"))
    )
    (net (code "67") (name "Net-(J1-CNTR)") (class "Default")
      (node (ref "C539") (pin "1") (pintype "passive"))
      (node (ref "J1") (pin "1") (pinfunction "CNTR_1") (pintype "passive"))
    )
    (net (code "68") (name "Net-(J3-CNTR)") (class "Default")
      (node (ref "AT68") (pin "3") (pinfunction "IN/OUT_3") (pintype "passive"))
      (node (ref "J3") (pin "1") (pinfunction "CNTR_1") (pintype "passive"))
    )
    (net (code "69") (name "Net-(L253-Pad1)") (class "Default")
      (node (ref "L253") (pin "1") (pinfunction "1_1") (pintype "passive"))
      (node (ref "R674") (pin "2") (pintype "passive"))
    )
    (net (code "70") (name "Net-(R33-Pad1)") (class "Default")
      (node (ref "R33") (pin "1") (pintype "passive"))
      (node (ref "R610") (pin "1") (pintype "passive"))
      (node (ref "U51") (pin "2") (pintype "passive"))
    )
    (net (code "71") (name "Net-(R34-Pad1)") (class "Default")
      (node (ref "R34") (pin "1") (pintype "passive"))
      (node (ref "R611") (pin "1") (pintype "passive"))
      (node (ref "U51") (pin "4") (pintype "passive"))
    )
    (net (code "72") (name "Net-(R37-Pad1)") (class "Default")
      (node (ref "R37") (pin "1") (pintype "passive"))
      (node (ref "R612") (pin "1") (pintype "passive"))
      (node (ref "U51") (pin "6") (pintype "passive"))
    )
    (net (code "73") (name "Net-(R40-Pad1)") (class "Default")
      (node (ref "R40") (pin "1") (pintype "passive"))
      (node (ref "R613") (pin "1") (pintype "passive"))
      (node (ref "U51") (pin "12") (pintype "passive"))
    )
    (net (code "74") (name "Net-(R42-Pad1)") (class "Default")
      (node (ref "R42") (pin "1") (pintype "passive"))
      (node (ref "R614") (pin "1") (pintype "passive"))
      (node (ref "U51") (pin "10") (pintype "passive"))
    )
    (net (code "75") (name "Net-(R44-Pad1)") (class "Default")
      (node (ref "R44") (pin "1") (pintype "passive"))
      (node (ref "R615") (pin "1") (pintype "passive"))
      (node (ref "U51") (pin "8") (pintype "passive"))
    )
    (net (code "76") (name "Net-(R45-Pad1)") (class "Default")
      (node (ref "R45") (pin "1") (pintype "passive"))
      (node (ref "R653") (pin "1") (pintype "passive"))
      (node (ref "U27") (pin "1") (pintype "passive"))
      (node (ref "U29") (pin "2") (pintype "passive"))
    )
    (net (code "77") (name "Net-(R46-Pad1)") (class "Default")
      (node (ref "R46") (pin "1") (pintype "passive"))
      (node (ref "R654") (pin "1") (pintype "passive"))
      (node (ref "U27") (pin "3") (pintype "passive"))
      (node (ref "U29") (pin "4") (pintype "passive"))
    )
    (net (code "78") (name "Net-(R49-Pad1)") (class "Default")
      (node (ref "R49") (pin "1") (pintype "passive"))
      (node (ref "R655") (pin "1") (pintype "passive"))
      (node (ref "U27") (pin "5") (pintype "passive"))
      (node (ref "U29") (pin "6") (pintype "passive"))
    )
    (net (code "79") (name "Net-(R50-Pad1)") (class "Default")
      (node (ref "R50") (pin "1") (pintype "passive"))
      (node (ref "R656") (pin "1") (pintype "passive"))
      (node (ref "U27") (pin "13") (pintype "passive"))
      (node (ref "U29") (pin "12") (pintype "passive"))
    )
    (net (code "80") (name "Net-(R51-Pad1)") (class "Default")
      (node (ref "R51") (pin "1") (pintype "passive"))
      (node (ref "R657") (pin "1") (pintype "passive"))
      (node (ref "U27") (pin "11") (pintype "passive"))
      (node (ref "U29") (pin "10") (pintype "passive"))
    )
    (net (code "81") (name "Net-(R52-Pad1)") (class "Default")
      (node (ref "R52") (pin "1") (pintype "passive"))
      (node (ref "R658") (pin "1") (pintype "passive"))
      (node (ref "U27") (pin "9") (pintype "passive"))
      (node (ref "U29") (pin "8") (pintype "passive"))
    )
    (net (code "82") (name "Net-(R312-Pad1)") (class "Default")
      (node (ref "R312") (pin "1") (pintype "passive"))
      (node (ref "R378") (pin "1") (pintype "passive"))
      (node (ref "U27") (pin "6") (pintype "passive"))
    )
    (net (code "83") (name "Net-(R313-Pad1)") (class "Default")
      (node (ref "R313") (pin "1") (pintype "passive"))
      (node (ref "R379") (pin "1") (pintype "passive"))
      (node (ref "U27") (pin "12") (pintype "passive"))
    )
    (net (code "84") (name "Net-(R314-Pad1)") (class "Default")
      (node (ref "R314") (pin "1") (pintype "passive"))
      (node (ref "R445") (pin "1") (pintype "passive"))
      (node (ref "U27") (pin "10") (pintype "passive"))
    )
    (net (code "85") (name "Net-(R369-Pad1)") (class "Default")
      (node (ref "R369") (pin "1") (pintype "passive"))
      (node (ref "R446") (pin "1") (pintype "passive"))
      (node (ref "U27") (pin "8") (pintype "passive"))
    )
    (net (code "86") (name "Net-(R376-Pad1)") (class "Default")
      (node (ref "R376") (pin "1") (pintype "passive"))
      (node (ref "R8") (pin "1") (pintype "passive"))
      (node (ref "U27") (pin "2") (pintype "passive"))
    )
    (net (code "87") (name "Net-(R377-Pad1)") (class "Default")
      (node (ref "R377") (pin "1") (pintype "passive"))
      (node (ref "R9") (pin "1") (pintype "passive"))
      (node (ref "U27") (pin "4") (pintype "passive"))
    )
    (net (code "88") (name "Net-(U26-OE1)") (class "Default")
      (node (ref "R368") (pin "1") (pintype "passive"))
      (node (ref "U26") (pin "6") (pinfunction "OE1_6") (pintype "passive"))
    )
    (net (code "89") (name "Net-(U36-RF1)") (class "Default")
      (node (ref "C515") (pin "2") (pintype "passive"))
      (node (ref "U36") (pin "9") (pinfunction "RF1_9") (pintype "passive"))
    )
    (net (code "90") (name "Net-(U36-RF2)") (class "Default")
      (node (ref "C359") (pin "1") (pintype "passive"))
      (node (ref "U36") (pin "12") (pinfunction "RF2_12") (pintype "passive"))
    )
    (net (code "91") (name "Net-(U36-RFC)") (class "Default")
      (node (ref "C539") (pin "2") (pintype "passive"))
      (node (ref "U36") (pin "3") (pinfunction "RFC_3") (pintype "passive"))
    )
    (net (code "92") (name "Net-(U36-Vctl)") (class "Default")
      (node (ref "C976") (pin "1") (pintype "passive"))
      (node (ref "R674") (pin "1") (pintype "passive"))
      (node (ref "U36") (pin "2") (pinfunction "Vctl_2") (pintype "passive"))
    )
    (net (code "93") (name "Net-(U36-Vdd)") (class "Default")
      (node (ref "C972") (pin "1") (pintype "passive"))
      (node (ref "C975") (pin "2") (pintype "passive"))
      (node (ref "L251") (pin "1") (pinfunction "1_1") (pintype "passive"))
      (node (ref "R606") (pin "1") (pintype "passive"))
      (node (ref "U36") (pin "1") (pinfunction "Vdd_1") (pintype "passive"))
    )
    (net (code "94") (name "unconnected-(U26-~{Y}6-Pad9)") (class "Default")
      (node (ref "U26") (pin "9") (pinfunction "~{Y}6_9") (pintype "passive"))
    )
    (net (code "95") (name "unconnected-(U26-~{Y}7-Pad7)") (class "Default")
      (node (ref "U26") (pin "7") (pinfunction "~{Y}7_7") (pintype "passive"))
    )
  )
)
